# adcAlpha.net
KiCad netlist of a schematic drawn in EAGLE
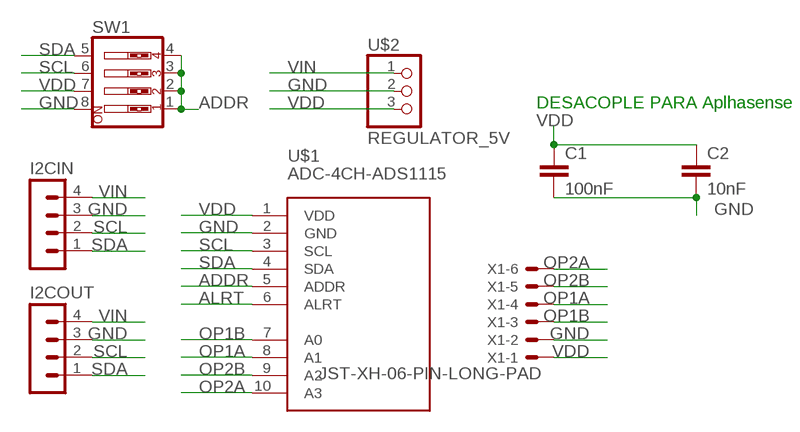
[diagram p0: schematic, sheet 1]

(export (version "E")
  (design (tool "Eeschema 10.0.6"))
  (components
    (comp (ref "C1")
      (value "100nF")
      (footprint "eagle-import:CAP-PTH-SMALL-KIT")
      (libsource (lib "eagle-import") (part "0.1UF-KIT-EZ-50V-20%"))
    )
    (comp (ref "C2")
      (value "10nF")
      (footprint "eagle-import:CAP-PTH-SMALL-KIT")
      (libsource (lib "eagle-import") (part "0.1UF-KIT-EZ-50V-20%"))
    )
    (comp (ref "I2CIN")
      (value "MA04-1")
      (footprint "eagle-import:MA04-1")
      (libsource (lib "eagle-import") (part "MA04-1"))
    )
    (comp (ref "I2COUT")
      (value "MA04-1")
      (footprint "eagle-import:MA04-1")
      (libsource (lib "eagle-import") (part "MA04-1"))
    )
    (comp (ref "SW1")
      (value "SW_DIP-4")
      (footprint "eagle-import:EDG-04")
      (libsource (lib "eagle-import") (part "SW_DIP-4"))
    )
    (comp (ref "U$1")
      (value "ADC-4CH-ADS1115")
      (footprint "eagle-import:ADC-4CH-ADS1115")
      (libsource (lib "eagle-import") (part "ADC-4CH-ADS1115"))
    )
    (comp (ref "U$2")
      (value "REGULATOR_5V")
      (footprint "eagle-import:1X03")
      (libsource (lib "eagle-import") (part "REGULATOR_5V"))
    )
    (comp (ref "X1")
      (value "JST-XH-06-PIN-LONG-PAD")
      (footprint "eagle-import:JST-XH-06-PACKAGE-LONG-PAD")
      (libsource (lib "eagle-import") (part "JST-XH-06-PIN-LONG-PAD"))
    )
  )
  (nets
    (net (code "1") (name "/ADDR") (class "Default")
      (node (ref "SW1") (pin "1") (pinfunction "1_1") (pintype "passive"))
      (node (ref "SW1") (pin "2") (pinfunction "2_2") (pintype "passive"))
      (node (ref "SW1") (pin "3") (pinfunction "3_3") (pintype "passive"))
      (node (ref "SW1") (pin "4") (pinfunction "4_4") (pintype "passive"))
      (node (ref "U$1") (pin "5") (pinfunction "ADDR_5") (pintype "bidirectional"))
    )
    (net (code "2") (name "/ALRT") (class "Default")
      (node (ref "U$1") (pin "6") (pinfunction "ALRT_6") (pintype "bidirectional"))
    )
    (net (code "3") (name "/GND") (class "Default")
      (node (ref "C1") (pin "2") (pinfunction "2_2") (pintype "passive"))
      (node (ref "C2") (pin "2") (pinfunction "2_2") (pintype "passive"))
      (node (ref "I2CIN") (pin "3") (pinfunction "3_3") (pintype "passive"))
      (node (ref "I2COUT") (pin "3") (pinfunction "3_3") (pintype "passive"))
      (node (ref "SW1") (pin "8") (pinfunction "8_8") (pintype "passive"))
      (node (ref "U$1") (pin "2") (pinfunction "GND_2") (pintype "power_in"))
      (node (ref "U$2") (pin "2") (pinfunction "GND_2") (pintype "passive"))
      (node (ref "X1") (pin "2") (pinfunction "S_2") (pintype "passive"))
    )
    (net (code "4") (name "/OP1A") (class "Default")
      (node (ref "U$1") (pin "8") (pinfunction "A1_8") (pintype "input"))
      (node (ref "X1") (pin "4") (pinfunction "S_4") (pintype "passive"))
    )
    (net (code "5") (name "/OP1B") (class "Default")
      (node (ref "U$1") (pin "7") (pinfunction "A0_7") (pintype "input"))
      (node (ref "X1") (pin "3") (pinfunction "S_3") (pintype "passive"))
    )
    (net (code "6") (name "/OP2A") (class "Default")
      (node (ref "U$1") (pin "10") (pinfunction "A3_10") (pintype "input"))
      (node (ref "X1") (pin "6") (pinfunction "S_6") (pintype "passive"))
    )
    (net (code "7") (name "/OP2B") (class "Default")
      (node (ref "U$1") (pin "9") (pinfunction "A2_9") (pintype "input"))
      (node (ref "X1") (pin "5") (pinfunction "S_5") (pintype "passive"))
    )
    (net (code "8") (name "/SCL") (class "Default")
      (node (ref "I2CIN") (pin "2") (pinfunction "2_2") (pintype "passive"))
      (node (ref "I2COUT") (pin "2") (pinfunction "2_2") (pintype "passive"))
      (node (ref "SW1") (pin "6") (pinfunction "6_6") (pintype "passive"))
      (node (ref "U$1") (pin "3") (pinfunction "SCL_3") (pintype "bidirectional"))
    )
    (net (code "9") (name "/SDA") (class "Default")
      (node (ref "I2CIN") (pin "1") (pinfunction "1_1") (pintype "passive"))
      (node (ref "I2COUT") (pin "1") (pinfunction "1_1") (pintype "passive"))
      (node (ref "SW1") (pin "5") (pinfunction "5_5") (pintype "passive"))
      (node (ref "U$1") (pin "4") (pinfunction "SDA_4") (pintype "bidirectional"))
    )
    (net (code "10") (name "/VDD") (class "Default")
      (node (ref "C1") (pin "1") (pinfunction "1_1") (pintype "passive"))
      (node (ref "C2") (pin "1") (pinfunction "1_1") (pintype "passive"))
      (node (ref "SW1") (pin "7") (pinfunction "7_7") (pintype "passive"))
      (node (ref "U$1") (pin "1") (pinfunction "VDD_1") (pintype "power_in"))
      (node (ref "U$2") (pin "3") (pinfunction "OUT5V_3") (pintype "passive"))
      (node (ref "X1") (pin "1") (pinfunction "S_1") (pintype "passive"))
    )
    (net (code "11") (name "/VIN") (class "Default")
      (node (ref "I2CIN") (pin "4") (pinfunction "4_4") (pintype "passive"))
      (node (ref "I2COUT") (pin "4") (pinfunction "4_4") (pintype "passive"))
      (node (ref "U$2") (pin "1") (pinfunction "IN_1") (pintype "passive"))
    )
  )
)
